# monoblink_wifi_v2.net
KiCad netlist of a schematic drawn in EAGLE
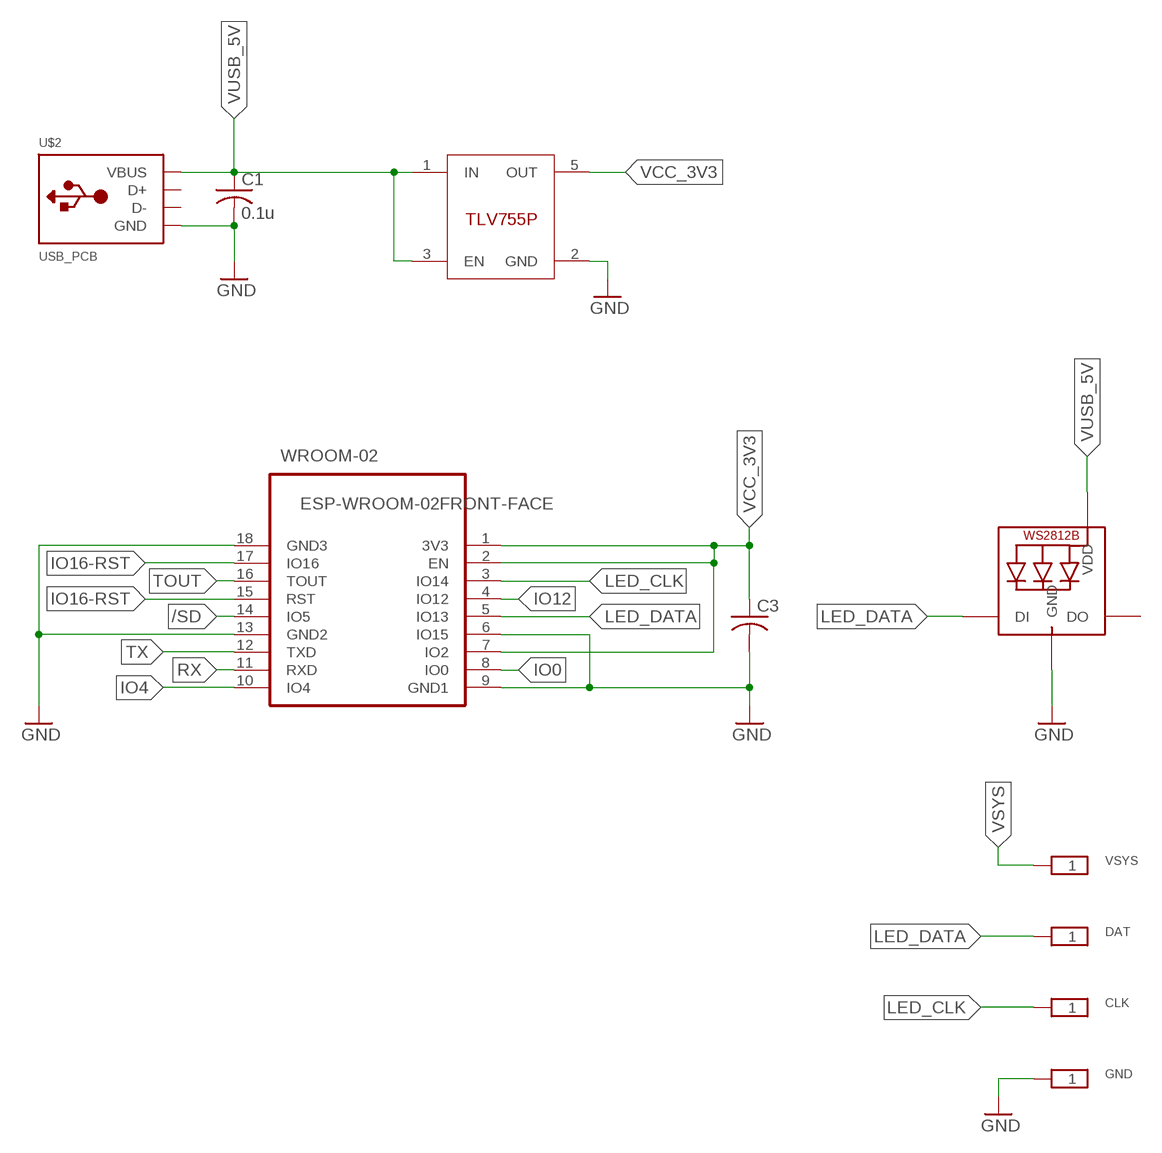
[diagram p0: schematic, sheet 1]

(export (version "E")
  (design (tool "Eeschema 10.0.6"))
  (components
    (comp (ref "C1")
      (value "0.1u")
      (footprint "eagle-import:C0603")
      (libsource (lib "eagle-import") (part "C-USC0603"))
    )
    (comp (ref "C3")
      (value "C-USC0603")
      (footprint "eagle-import:C0603")
      (libsource (lib "eagle-import") (part "C-USC0603"))
    )
    (comp (ref "CLK")
      (value "TESTPAD_PROG")
      (footprint "eagle-import:TP1.5MM")
      (libsource (lib "eagle-import") (part "TESTPAD_PROG"))
    )
    (comp (ref "DAT")
      (value "TESTPAD_PROG")
      (footprint "eagle-import:TP1.5MM")
      (libsource (lib "eagle-import") (part "TESTPAD_PROG"))
    )
    (comp (ref "GND")
      (value "TESTPAD_PROG")
      (footprint "eagle-import:TP1.5MM")
      (libsource (lib "eagle-import") (part "TESTPAD_PROG"))
    )
    (comp (ref "LDO")
      (value "TLV755P")
      (footprint "eagle-import:SOT23-5")
      (libsource (lib "eagle-import") (part "TLV755P"))
    )
    (comp (ref "LED")
      (value "WS2812B5050")
      (footprint "eagle-import:WS2812B")
      (libsource (lib "eagle-import") (part "WS2812B5050"))
    )
    (comp (ref "U$2")
      (value "USB_PCB")
      (footprint "eagle-import:USB_PADS")
      (libsource (lib "eagle-import") (part "USB_PCB"))
    )
    (comp (ref "VSYS")
      (value "TESTPAD_PROG")
      (footprint "eagle-import:TP1.5MM")
      (libsource (lib "eagle-import") (part "TESTPAD_PROG"))
    )
    (comp (ref "WROOM-02")
      (value "ESP-WROOM-02FRONT-FACE")
      (footprint "eagle-import:FRONT-FACE")
      (libsource (lib "eagle-import") (part "ESP-WROOM-02FRONT-FACE"))
    )
  )
  (nets
    (net (code "1") (name "GND") (class "Default")
      (node (ref "C1") (pin "2") (pinfunction "2_2") (pintype "passive"))
      (node (ref "C3") (pin "2") (pinfunction "2_2") (pintype "passive"))
      (node (ref "GND") (pin "1") (pinfunction "1_1") (pintype "bidirectional"))
      (node (ref "LDO") (pin "2") (pinfunction "GND_2") (pintype "bidirectional"))
      (node (ref "LED") (pin "3-GND") (pinfunction "GND_3-GND") (pintype "power_in"))
      (node (ref "U$2") (pin "GND") (pinfunction "GND_GND") (pintype "power_in"))
      (node (ref "WROOM-02") (pin "13") (pinfunction "GND2_13") (pintype "power_in"))
      (node (ref "WROOM-02") (pin "18") (pinfunction "GND3_18") (pintype "power_in"))
      (node (ref "WROOM-02") (pin "6") (pinfunction "IO15_6") (pintype "bidirectional"))
      (node (ref "WROOM-02") (pin "9") (pinfunction "GND1_9") (pintype "power_in"))
    )
    (net (code "2") (name "IO0") (class "Default")
      (node (ref "WROOM-02") (pin "8") (pinfunction "IO0_8") (pintype "bidirectional"))
    )
    (net (code "3") (name "IO4") (class "Default")
      (node (ref "WROOM-02") (pin "10") (pinfunction "IO4_10") (pintype "bidirectional"))
    )
    (net (code "4") (name "IO12") (class "Default")
      (node (ref "WROOM-02") (pin "4") (pinfunction "IO12_4") (pintype "bidirectional"))
    )
    (net (code "5") (name "IO16-RST") (class "Default")
      (node (ref "WROOM-02") (pin "15") (pinfunction "RST_15") (pintype "bidirectional"))
      (node (ref "WROOM-02") (pin "17") (pinfunction "IO16_17") (pintype "bidirectional"))
    )
    (net (code "6") (name "LED_CLK") (class "Default")
      (node (ref "CLK") (pin "1") (pinfunction "1_1") (pintype "bidirectional"))
      (node (ref "WROOM-02") (pin "3") (pinfunction "IO14_3") (pintype "bidirectional"))
    )
    (net (code "7") (name "LED_DATA") (class "Default")
      (node (ref "DAT") (pin "1") (pinfunction "1_1") (pintype "bidirectional"))
      (node (ref "LED") (pin "4-DIN") (pinfunction "DI_4-DIN") (pintype "input"))
      (node (ref "WROOM-02") (pin "5") (pinfunction "IO13_5") (pintype "bidirectional"))
    )
    (net (code "8") (name "RX") (class "Default")
      (node (ref "WROOM-02") (pin "11") (pinfunction "RXD_11") (pintype "bidirectional"))
    )
    (net (code "9") (name "TOUT") (class "Default")
      (node (ref "WROOM-02") (pin "16") (pinfunction "TOUT_16") (pintype "bidirectional"))
    )
    (net (code "10") (name "TX") (class "Default")
      (node (ref "WROOM-02") (pin "12") (pinfunction "TXD_12") (pintype "bidirectional"))
    )
    (net (code "11") (name "VCC_3V3") (class "Default")
      (node (ref "C3") (pin "1") (pinfunction "1_1") (pintype "passive"))
      (node (ref "LDO") (pin "5") (pinfunction "OUT_5") (pintype "bidirectional"))
      (node (ref "WROOM-02") (pin "1") (pinfunction "3V3_1") (pintype "power_in"))
      (node (ref "WROOM-02") (pin "2") (pinfunction "EN_2") (pintype "bidirectional"))
      (node (ref "WROOM-02") (pin "7") (pinfunction "IO2_7") (pintype "bidirectional"))
    )
    (net (code "12") (name "VSYS") (class "Default")
      (node (ref "VSYS") (pin "1") (pinfunction "1_1") (pintype "bidirectional"))
    )
    (net (code "13") (name "VUSB_5V") (class "Default")
      (node (ref "C1") (pin "1") (pinfunction "1_1") (pintype "passive"))
      (node (ref "LDO") (pin "1") (pinfunction "IN_1") (pintype "bidirectional"))
      (node (ref "LDO") (pin "3") (pinfunction "EN_3") (pintype "bidirectional"))
      (node (ref "LED") (pin "1-VDD") (pinfunction "VDD_1-VDD") (pintype "power_in"))
      (node (ref "U$2") (pin "V_SUPPLY") (pinfunction "VBUS_V_SUPPLY") (pintype "power_in"))
    )
    (net (code "14") (name "unconnected-(LED-DO-Pad2-DOUT)") (class "Default")
      (node (ref "LED") (pin "2-DOUT") (pinfunction "DO_2-DOUT") (pintype "output"))
    )
    (net (code "15") (name "unconnected-(U$2-PadD+)") (class "Default")
      (node (ref "U$2") (pin "D+") (pinfunction "D+_D+") (pintype "bidirectional"))
    )
    (net (code "16") (name "unconnected-(U$2-PadD-)") (class "Default")
      (node (ref "U$2") (pin "D-") (pinfunction "D-_D-") (pintype "bidirectional"))
    )
    (net (code "17") (name "{slash}SD") (class "Default")
      (node (ref "WROOM-02") (pin "14") (pinfunction "IO5_14") (pintype "open_collector"))
    )
  )
)
